# BLE_--_HM-10_ATtiny85_Combo_--_v02.net
KiCad netlist of a schematic drawn in EAGLE
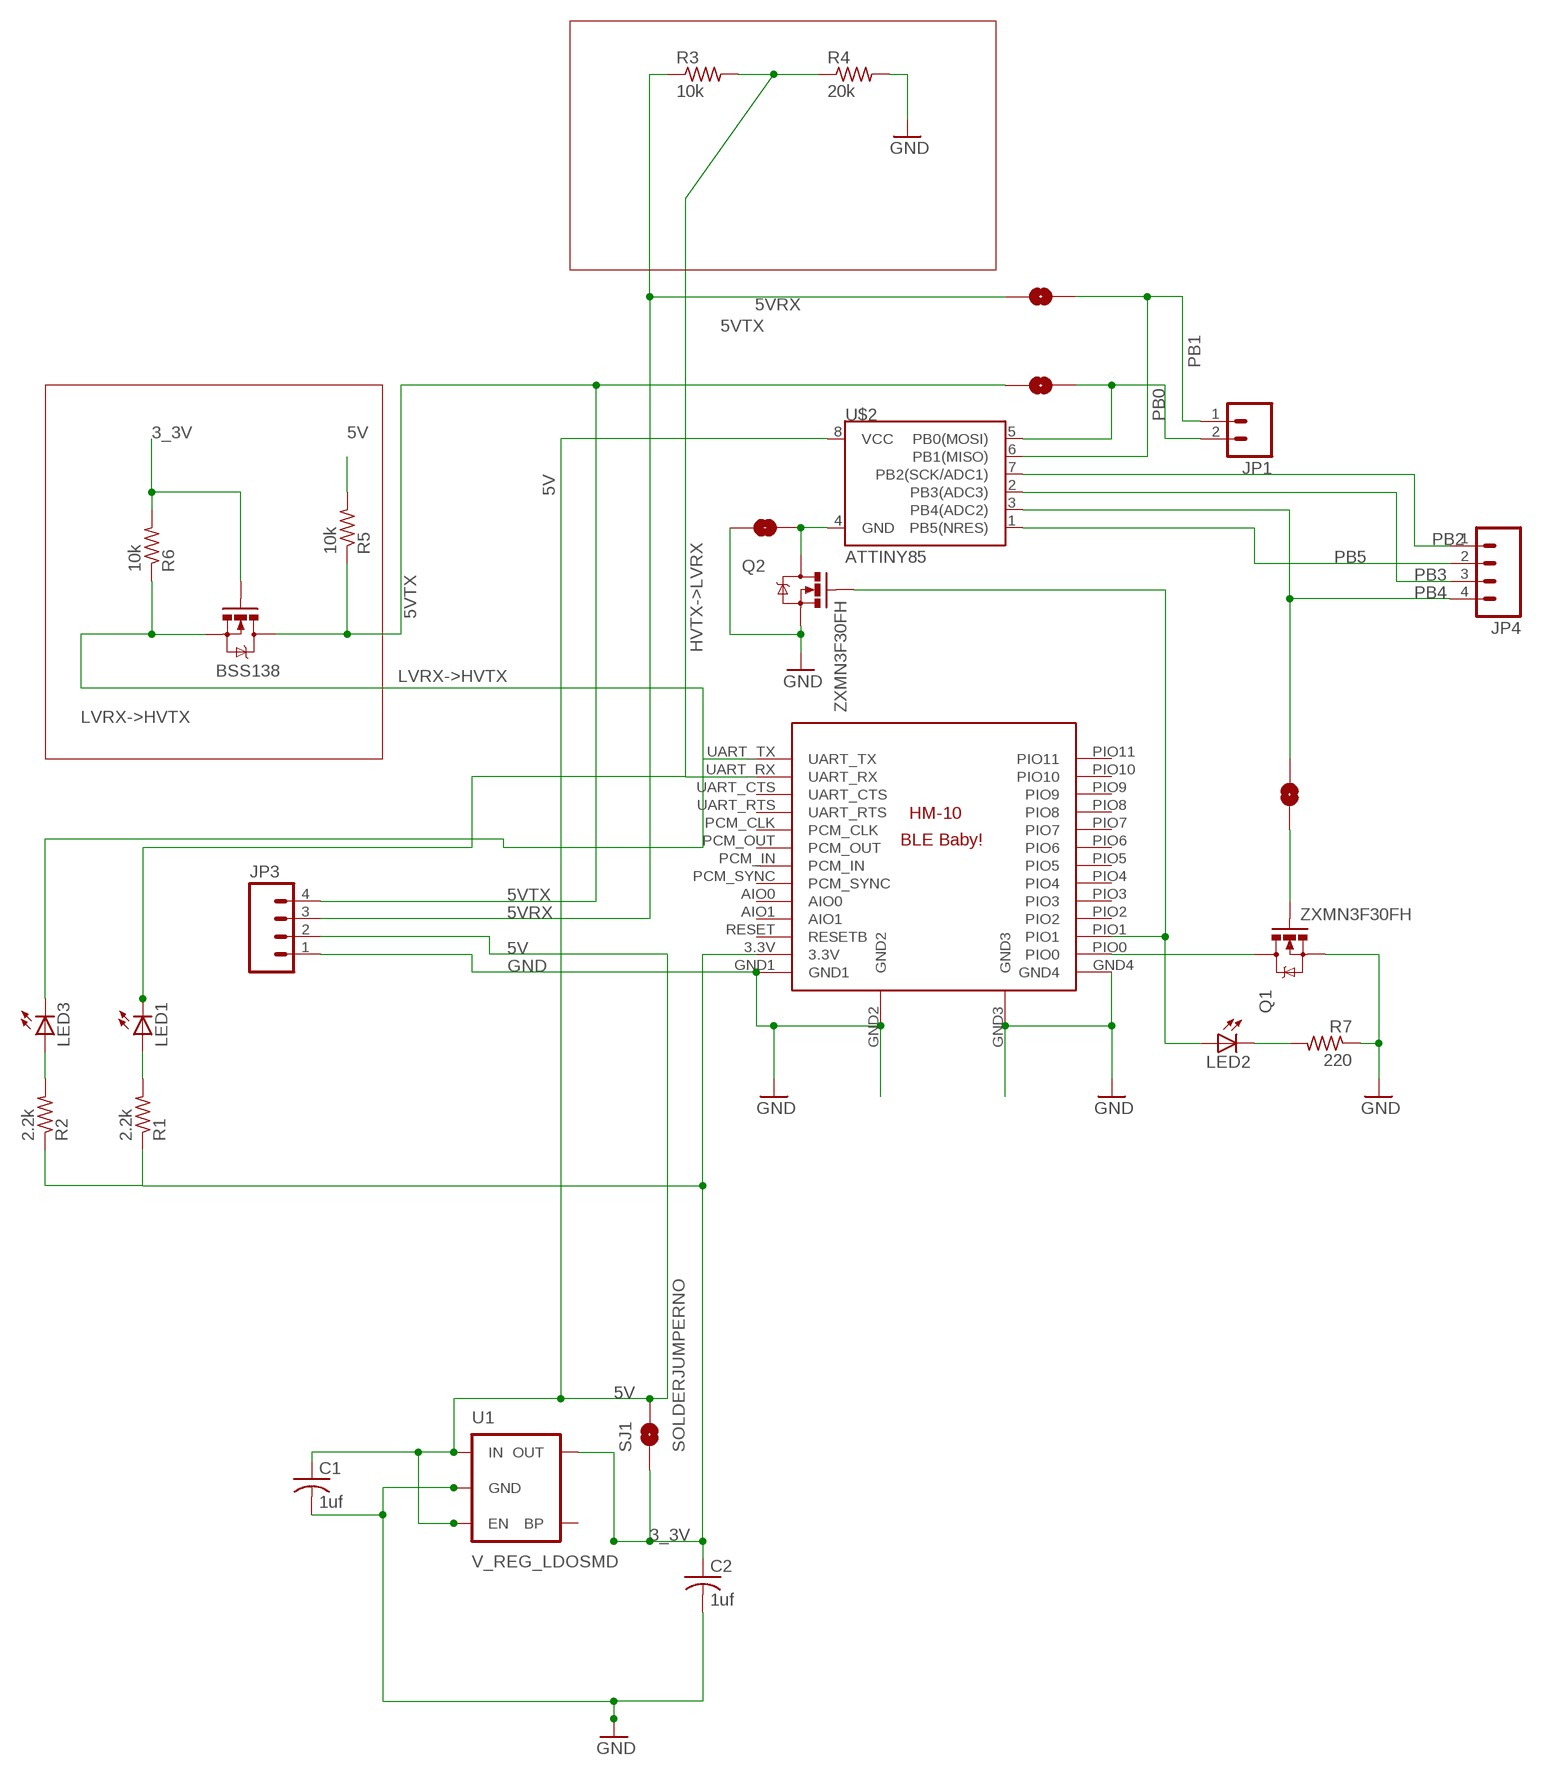
[diagram p0: schematic, sheet 1]

(export (version "E")
  (design (tool "Eeschema 10.0.6"))
  (components
    (comp (ref "BSS138")
      (value "MOSFET-NCHANNELSMD")
      (footprint "eagle-import:SOT23-3")
      (libsource (lib "eagle-import") (part "MOSFET-NCHANNELSMD"))
    )
    (comp (ref "C1")
      (value "1uf")
      (footprint "eagle-import:C0402")
      (libsource (lib "eagle-import") (part "C-USC0402"))
    )
    (comp (ref "C2")
      (value "1uf")
      (footprint "eagle-import:C0402")
      (libsource (lib "eagle-import") (part "C-USC0402"))
    )
    (comp (ref "JP1")
      (value "M02PTH")
      (footprint "eagle-import:1X02")
      (libsource (lib "eagle-import") (part "M02PTH"))
    )
    (comp (ref "JP3")
      (value "M04PTH")
      (footprint "eagle-import:1X04")
      (libsource (lib "eagle-import") (part "M04PTH"))
    )
    (comp (ref "JP4")
      (value "M04PTH")
      (footprint "eagle-import:1X04")
      (libsource (lib "eagle-import") (part "M04PTH"))
    )
    (comp (ref "LED1")
      (value "LED0603")
      (footprint "eagle-import:LED-0603")
      (libsource (lib "eagle-import") (part "LED0603"))
    )
    (comp (ref "LED2")
      (value "LED0603")
      (footprint "eagle-import:LED-0603")
      (libsource (lib "eagle-import") (part "LED0603"))
    )
    (comp (ref "LED3")
      (value "LED0603")
      (footprint "eagle-import:LED-0603")
      (libsource (lib "eagle-import") (part "LED0603"))
    )
    (comp (ref "Q1")
      (value "ZXMN3F30FH")
      (footprint "eagle-import:SOT23-3")
      (libsource (lib "eagle-import") (part "MOSFET-NCHANNELSMD"))
    )
    (comp (ref "Q2")
      (value "ZXMN3F30FH")
      (footprint "eagle-import:SOT23-3")
      (libsource (lib "eagle-import") (part "MOSFET-NCHANNELSMD"))
    )
    (comp (ref "R1")
      (value "2.2k")
      (footprint "eagle-import:R0402")
      (libsource (lib "eagle-import") (part "R-US_R0402"))
    )
    (comp (ref "R2")
      (value "2.2k")
      (footprint "eagle-import:R0402")
      (libsource (lib "eagle-import") (part "R-US_R0402"))
    )
    (comp (ref "R3")
      (value "10k")
      (footprint "eagle-import:R0402")
      (libsource (lib "eagle-import") (part "R-US_R0402"))
    )
    (comp (ref "R4")
      (value "20k")
      (footprint "eagle-import:R0402")
      (libsource (lib "eagle-import") (part "R-US_R0402"))
    )
    (comp (ref "R5")
      (value "10k")
      (footprint "eagle-import:R0402")
      (libsource (lib "eagle-import") (part "R-US_R0402"))
    )
    (comp (ref "R6")
      (value "10k")
      (footprint "eagle-import:R0402")
      (libsource (lib "eagle-import") (part "R-US_R0402"))
    )
    (comp (ref "R7")
      (value "220")
      (footprint "eagle-import:R0402")
      (libsource (lib "eagle-import") (part "R-US_R0402"))
    )
    (comp (ref "SJ1")
      (value "SOLDERJUMPERNO")
      (footprint "eagle-import:SJ_2S-NO")
      (libsource (lib "eagle-import") (part "SOLDERJUMPERNO"))
    )
    (comp (ref "SJ2")
      (value "SOLDERJUMPERNO")
      (footprint "eagle-import:SJ_2S-NO")
      (libsource (lib "eagle-import") (part "SOLDERJUMPERNO"))
    )
    (comp (ref "SJ3")
      (value "SOLDERJUMPERNO")
      (footprint "eagle-import:SJ_2S-NO")
      (libsource (lib "eagle-import") (part "SOLDERJUMPERNO"))
    )
    (comp (ref "SJ4")
      (value "SOLDERJUMPERNO")
      (footprint "eagle-import:SJ_2S-NO")
      (libsource (lib "eagle-import") (part "SOLDERJUMPERNO"))
    )
    (comp (ref "SJ5")
      (value "SOLDERJUMPERNO")
      (footprint "eagle-import:SJ_2S-NO")
      (libsource (lib "eagle-import") (part "SOLDERJUMPERNO"))
    )
    (comp (ref "U$1")
      (value "BLE-HM10_NO_SPI")
      (footprint "eagle-import:BLE-HM10_NO_SPI")
      (libsource (lib "eagle-import") (part "BLE-HM10_NO_SPI"))
    )
    (comp (ref "U$2")
      (value "ATTINY85")
      (footprint "eagle-import:SO08-EIAJ")
      (libsource (lib "eagle-import") (part "ATTINY45"))
    )
    (comp (ref "U1")
      (value "V_REG_LDOSMD")
      (footprint "eagle-import:SOT23-5")
      (libsource (lib "eagle-import") (part "V_REG_LDOSMD"))
    )
  )
  (nets
    (net (code "1") (name "/3_3V") (class "Default")
      (node (ref "BSS138") (pin "1") (pinfunction "G_1") (pintype "passive"))
      (node (ref "C2") (pin "1") (pinfunction "1_1") (pintype "passive"))
      (node (ref "R1") (pin "1") (pinfunction "1_1") (pintype "passive"))
      (node (ref "R2") (pin "1") (pinfunction "1_1") (pintype "passive"))
      (node (ref "R6") (pin "2") (pinfunction "2_2") (pintype "passive"))
      (node (ref "SJ1") (pin "1") (pinfunction "1_1") (pintype "passive"))
      (node (ref "U$1") (pin "3.3V") (pinfunction "3.3V_3.3V") (pintype "bidirectional"))
      (node (ref "U1") (pin "5") (pinfunction "OUT_5") (pintype "passive"))
    )
    (net (code "2") (name "/5V") (class "Default")
      (node (ref "C1") (pin "1") (pinfunction "1_1") (pintype "passive"))
      (node (ref "JP3") (pin "2") (pinfunction "2_2") (pintype "passive"))
      (node (ref "R5") (pin "2") (pinfunction "2_2") (pintype "passive"))
      (node (ref "SJ1") (pin "2") (pinfunction "2_2") (pintype "passive"))
      (node (ref "U$2") (pin "8") (pinfunction "VCC_8") (pintype "bidirectional"))
      (node (ref "U1") (pin "1") (pinfunction "IN_1") (pintype "input"))
      (node (ref "U1") (pin "3") (pinfunction "EN_3") (pintype "input"))
    )
    (net (code "3") (name "/5VRX") (class "Default")
      (node (ref "JP3") (pin "3") (pinfunction "3_3") (pintype "passive"))
      (node (ref "R3") (pin "1") (pinfunction "1_1") (pintype "passive"))
      (node (ref "SJ3") (pin "2") (pinfunction "2_2") (pintype "passive"))
    )
    (net (code "4") (name "/5VTX") (class "Default")
      (node (ref "BSS138") (pin "3") (pinfunction "D_3") (pintype "passive"))
      (node (ref "JP3") (pin "4") (pinfunction "4_4") (pintype "passive"))
      (node (ref "R5") (pin "1") (pinfunction "1_1") (pintype "passive"))
      (node (ref "SJ2") (pin "2") (pinfunction "2_2") (pintype "passive"))
    )
    (net (code "5") (name "/HVTX->LVRX") (class "Default")
      (node (ref "LED1") (pin "C") (pinfunction "C_C") (pintype "passive"))
      (node (ref "R3") (pin "2") (pinfunction "2_2") (pintype "passive"))
      (node (ref "R4") (pin "1") (pinfunction "1_1") (pintype "passive"))
      (node (ref "U$1") (pin "UART_RX") (pinfunction "UART_RX_UART_RX") (pintype "bidirectional"))
    )
    (net (code "6") (name "/LVRX->HVTX") (class "Default")
      (node (ref "BSS138") (pin "2") (pinfunction "S_2") (pintype "passive"))
      (node (ref "LED3") (pin "C") (pinfunction "C_C") (pintype "passive"))
      (node (ref "R6") (pin "1") (pinfunction "1_1") (pintype "passive"))
      (node (ref "U$1") (pin "UART_TX") (pinfunction "UART_TX_UART_TX") (pintype "bidirectional"))
    )
    (net (code "7") (name "/PB0") (class "Default")
      (node (ref "JP1") (pin "2") (pinfunction "2_2") (pintype "passive"))
      (node (ref "SJ2") (pin "1") (pinfunction "1_1") (pintype "passive"))
      (node (ref "U$2") (pin "5") (pinfunction "PB0(MOSI)_5") (pintype "bidirectional"))
    )
    (net (code "8") (name "/PB1") (class "Default")
      (node (ref "JP1") (pin "1") (pinfunction "1_1") (pintype "passive"))
      (node (ref "SJ3") (pin "1") (pinfunction "1_1") (pintype "passive"))
      (node (ref "U$2") (pin "6") (pinfunction "PB1(MISO)_6") (pintype "bidirectional"))
    )
    (net (code "9") (name "/PB2") (class "Default")
      (node (ref "JP4") (pin "1") (pinfunction "1_1") (pintype "passive"))
      (node (ref "U$2") (pin "7") (pinfunction "PB2(SCK/ADC1)_7") (pintype "bidirectional"))
    )
    (net (code "10") (name "/PB3") (class "Default")
      (node (ref "JP4") (pin "3") (pinfunction "3_3") (pintype "passive"))
      (node (ref "U$2") (pin "2") (pinfunction "PB3(ADC3)_2") (pintype "bidirectional"))
    )
    (net (code "11") (name "/PB4") (class "Default")
      (node (ref "JP4") (pin "4") (pinfunction "4_4") (pintype "passive"))
      (node (ref "SJ4") (pin "1") (pinfunction "1_1") (pintype "passive"))
      (node (ref "U$2") (pin "3") (pinfunction "PB4(ADC2)_3") (pintype "bidirectional"))
    )
    (net (code "12") (name "/PB5") (class "Default")
      (node (ref "JP4") (pin "2") (pinfunction "2_2") (pintype "passive"))
      (node (ref "U$2") (pin "1") (pinfunction "PB5(NRES)_1") (pintype "bidirectional"))
    )
    (net (code "13") (name "GND") (class "Default")
      (node (ref "C1") (pin "2") (pinfunction "2_2") (pintype "passive"))
      (node (ref "C2") (pin "2") (pinfunction "2_2") (pintype "passive"))
      (node (ref "JP3") (pin "1") (pinfunction "1_1") (pintype "passive"))
      (node (ref "Q1") (pin "2") (pinfunction "S_2") (pintype "passive"))
      (node (ref "Q2") (pin "2") (pinfunction "S_2") (pintype "passive"))
      (node (ref "R4") (pin "2") (pinfunction "2_2") (pintype "passive"))
      (node (ref "R7") (pin "1") (pinfunction "1_1") (pintype "passive"))
      (node (ref "SJ5") (pin "1") (pinfunction "1_1") (pintype "passive"))
      (node (ref "U$1") (pin "GND1") (pinfunction "GND1_GND1") (pintype "bidirectional"))
      (node (ref "U$1") (pin "GND2") (pinfunction "GND2_GND2") (pintype "bidirectional"))
      (node (ref "U$1") (pin "GND3") (pinfunction "GND3_GND3") (pintype "bidirectional"))
      (node (ref "U$1") (pin "GND4") (pinfunction "GND4_GND4") (pintype "bidirectional"))
      (node (ref "U1") (pin "2") (pinfunction "GND_2") (pintype "input"))
    )
    (net (code "14") (name "Net-(LED1-PadA)") (class "Default")
      (node (ref "LED1") (pin "A") (pinfunction "A_A") (pintype "passive"))
      (node (ref "R1") (pin "2") (pinfunction "2_2") (pintype "passive"))
    )
    (net (code "15") (name "Net-(LED2-PadC)") (class "Default")
      (node (ref "LED2") (pin "C") (pinfunction "C_C") (pintype "passive"))
      (node (ref "R7") (pin "2") (pinfunction "2_2") (pintype "passive"))
    )
    (net (code "16") (name "Net-(LED3-PadA)") (class "Default")
      (node (ref "LED3") (pin "A") (pinfunction "A_A") (pintype "passive"))
      (node (ref "R2") (pin "2") (pinfunction "2_2") (pintype "passive"))
    )
    (net (code "17") (name "Net-(Q1-D)") (class "Default")
      (node (ref "Q1") (pin "3") (pinfunction "D_3") (pintype "passive"))
      (node (ref "U$1") (pin "PIO0") (pinfunction "PIO0_PIO0") (pintype "bidirectional"))
    )
    (net (code "18") (name "Net-(Q1-G)") (class "Default")
      (node (ref "Q1") (pin "1") (pinfunction "G_1") (pintype "passive"))
      (node (ref "SJ4") (pin "2") (pinfunction "2_2") (pintype "passive"))
    )
    (net (code "19") (name "Net-(Q2-D)") (class "Default")
      (node (ref "Q2") (pin "3") (pinfunction "D_3") (pintype "passive"))
      (node (ref "SJ5") (pin "2") (pinfunction "2_2") (pintype "passive"))
      (node (ref "U$2") (pin "4") (pinfunction "GND_4") (pintype "bidirectional"))
    )
    (net (code "20") (name "Net-(Q2-G)") (class "Default")
      (node (ref "LED2") (pin "A") (pinfunction "A_A") (pintype "passive"))
      (node (ref "Q2") (pin "1") (pinfunction "G_1") (pintype "passive"))
      (node (ref "U$1") (pin "PIO1") (pinfunction "PIO1_PIO1") (pintype "bidirectional"))
    )
    (net (code "21") (name "unconnected-(U$1-PadAIO0)") (class "Default")
      (node (ref "U$1") (pin "AIO0") (pinfunction "AIO0_AIO0") (pintype "bidirectional"))
    )
    (net (code "22") (name "unconnected-(U$1-PadAIO1)") (class "Default")
      (node (ref "U$1") (pin "AIO1") (pinfunction "AIO1_AIO1") (pintype "bidirectional"))
    )
    (net (code "23") (name "unconnected-(U$1-PadPCM_CLK)") (class "Default")
      (node (ref "U$1") (pin "PCM_CLK") (pinfunction "PCM_CLK_PCM_CLK") (pintype "bidirectional"))
    )
    (net (code "24") (name "unconnected-(U$1-PadPCM_IN)") (class "Default")
      (node (ref "U$1") (pin "PCM_IN") (pinfunction "PCM_IN_PCM_IN") (pintype "bidirectional"))
    )
    (net (code "25") (name "unconnected-(U$1-PadPCM_OUT)") (class "Default")
      (node (ref "U$1") (pin "PCM_OUT") (pinfunction "PCM_OUT_PCM_OUT") (pintype "bidirectional"))
    )
    (net (code "26") (name "unconnected-(U$1-PadPCM_SYNC)") (class "Default")
      (node (ref "U$1") (pin "PCM_SYNC") (pinfunction "PCM_SYNC_PCM_SYNC") (pintype "bidirectional"))
    )
    (net (code "27") (name "unconnected-(U$1-PadPIO2)") (class "Default")
      (node (ref "U$1") (pin "PIO2") (pinfunction "PIO2_PIO2") (pintype "bidirectional"))
    )
    (net (code "28") (name "unconnected-(U$1-PadPIO3)") (class "Default")
      (node (ref "U$1") (pin "PIO3") (pinfunction "PIO3_PIO3") (pintype "bidirectional"))
    )
    (net (code "29") (name "unconnected-(U$1-PadPIO4)") (class "Default")
      (node (ref "U$1") (pin "PIO4") (pinfunction "PIO4_PIO4") (pintype "bidirectional"))
    )
    (net (code "30") (name "unconnected-(U$1-PadPIO5)") (class "Default")
      (node (ref "U$1") (pin "PIO5") (pinfunction "PIO5_PIO5") (pintype "bidirectional"))
    )
    (net (code "31") (name "unconnected-(U$1-PadPIO6)") (class "Default")
      (node (ref "U$1") (pin "PIO6") (pinfunction "PIO6_PIO6") (pintype "bidirectional"))
    )
    (net (code "32") (name "unconnected-(U$1-PadPIO7)") (class "Default")
      (node (ref "U$1") (pin "PIO7") (pinfunction "PIO7_PIO7") (pintype "bidirectional"))
    )
    (net (code "33") (name "unconnected-(U$1-PadPIO8)") (class "Default")
      (node (ref "U$1") (pin "PIO8") (pinfunction "PIO8_PIO8") (pintype "bidirectional"))
    )
    (net (code "34") (name "unconnected-(U$1-PadPIO9)") (class "Default")
      (node (ref "U$1") (pin "PIO9") (pinfunction "PIO9_PIO9") (pintype "bidirectional"))
    )
    (net (code "35") (name "unconnected-(U$1-PadPIO10)") (class "Default")
      (node (ref "U$1") (pin "PIO10") (pinfunction "PIO10_PIO10") (pintype "bidirectional"))
    )
    (net (code "36") (name "unconnected-(U$1-PadPIO11)") (class "Default")
      (node (ref "U$1") (pin "PIO11") (pinfunction "PIO11_PIO11") (pintype "bidirectional"))
    )
    (net (code "37") (name "unconnected-(U$1-PadUART_CTS)") (class "Default")
      (node (ref "U$1") (pin "UART_CTS") (pinfunction "UART_CTS_UART_CTS") (pintype "bidirectional"))
    )
    (net (code "38") (name "unconnected-(U$1-PadUART_RTS)") (class "Default")
      (node (ref "U$1") (pin "UART_RTS") (pinfunction "UART_RTS_UART_RTS") (pintype "bidirectional"))
    )
    (net (code "39") (name "unconnected-(U$1-RESETB-PadRESET)") (class "Default")
      (node (ref "U$1") (pin "RESET") (pinfunction "RESETB_RESET") (pintype "bidirectional"))
    )
    (net (code "40") (name "unconnected-(U1-BP-Pad4)") (class "Default")
      (node (ref "U1") (pin "4") (pinfunction "BP_4") (pintype "input"))
    )
  )
)
